# RFE_Cellularv2_1.net
KiCad netlist of a schematic drawn in Altium Designer
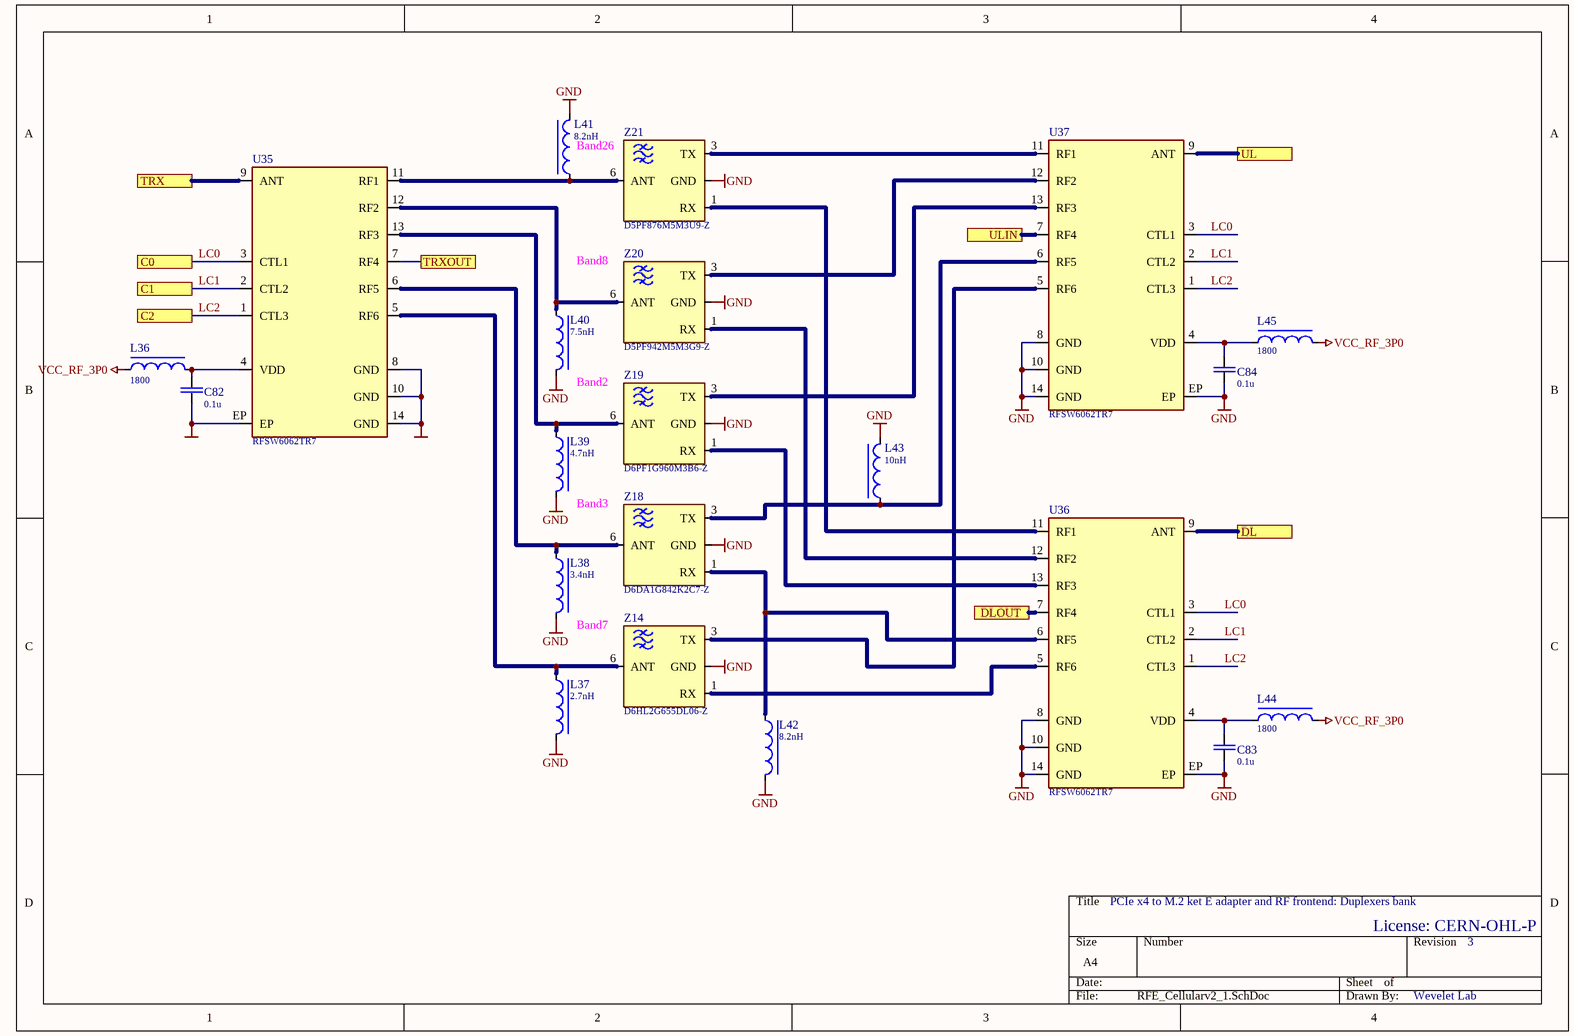
[diagram p0: RFE_Cellularv2_1.SchDoc]

(export (version "E")
  (design (tool "Eeschema 10.0.6"))
  (components
    (comp (ref "C82")
      (value "0.1u")
      (footprint "CAPC100X50X55L25N")
      (description "Capacitor, 0.1u, 25V, 10%, X7R, 0402")
      (fields
        (field (name "MANUFACTURER") "Murata Electronics")
        (field (name "Comment") "GRM155R71E104KE14D")
      )
      (libsource (lib "Capacitors") (part "GRM155R71E104KE14D"))
    )
    (comp (ref "C83")
      (value "0.1u")
      (footprint "CAPC100X50X55L25N")
      (description "Capacitor, 0.1u, 25V, 10%, X7R, 0402")
      (fields
        (field (name "MANUFACTURER") "Murata Electronics")
        (field (name "Comment") "GRM155R71E104KE14D")
      )
      (libsource (lib "Capacitors") (part "GRM155R71E104KE14D"))
    )
    (comp (ref "C84")
      (value "0.1u")
      (footprint "CAPC100X50X55L25N")
      (description "Capacitor, 0.1u, 25V, 10%, X7R, 0402")
      (fields
        (field (name "MANUFACTURER") "Murata Electronics")
        (field (name "Comment") "GRM155R71E104KE14D")
      )
      (libsource (lib "Capacitors") (part "GRM155R71E104KE14D"))
    )
    (comp (ref "L36")
      (value "1800")
      (footprint "INDC100X60X60L30N")
      (description "Ferrite bead, 1800Ohm@100MHz, 0,2A, 2.2Ohm, -55/+125, SMD0402")
      (fields (field (name "MANUFACTURER") "Murata Electronics") (field (name "Comment") "BLM15HD182SN1D"))
      (libsource (lib "") (part "BLM15HD182SN1D_1"))
    )
    (comp (ref "L37")
      (value "2.7nH")
      (footprint "INDC60X30X35L15N")
      (description "Inductor, 2.7n, 0.5A, 200mOhm, -55/+125, SMD0201")
      (fields (field (name "MANUFACTURER") "TDK") (field (name "Comment") "MLG0603P2N7CT000"))
      (libsource (lib "Inductor_Transformer") (part "MLG0603P2N7CT000"))
    )
    (comp (ref "L38")
      (value "3.4nH")
      (footprint "INDC60X30X35L15N")
      (description "Inductor, 3.4n, -55/+125, SMD0201")
      (fields (field (name "MANUFACTURER") "TDK") (field (name "Comment") "MLG0603P3N4BT000"))
      (libsource (lib "Inductor_Transformer") (part "MLG0603P3N4BT000"))
    )
    (comp (ref "L39")
      (value "4.7nH")
      (footprint "INDC60X30X35L15N")
      (description "Inductor, 4.7n, -55/+125, SMD0201")
      (fields (field (name "MANUFACTURER") "TDK") (field (name "Comment") "MLG0603P4N7HT000"))
      (libsource (lib "Inductor_Transformer") (part "MLG0603P4N7HT000"))
    )
    (comp (ref "L40")
      (value "7.5nH")
      (footprint "INDC60X30X35L15N")
      (description "Inductor, 7.5n, -55/+125, SMD0201")
      (fields (field (name "MANUFACTURER") "TDK") (field (name "Comment") "MLG0603P7N5HT000"))
      (libsource (lib "Inductor_Transformer") (part "MLG0603P7N5HT000"))
    )
    (comp (ref "L41")
      (value "8.2nH")
      (footprint "INDC60X30X35L15N")
      (description "Inductor, 8.2n, -55/+125, SMD0201")
      (fields (field (name "MANUFACTURER") "TDK") (field (name "Comment") "MLG0603P8N2HT000"))
      (libsource (lib "Inductor_Transformer") (part "MLG0603P8N2HT000"))
    )
    (comp (ref "L42")
      (value "8.2nH")
      (footprint "INDC60X30X35L15N")
      (description "Inductor, 8.2n, -55/+125, SMD0201")
      (fields (field (name "MANUFACTURER") "TDK") (field (name "Comment") "MLG0603P8N2HT000"))
      (libsource (lib "Inductor_Transformer") (part "MLG0603P8N2HT000"))
    )
    (comp (ref "L43")
      (value "10nH")
      (footprint "INDC60X30X35L15N")
      (description "Inductor, 10n, -55/+125, SMD0201")
      (fields (field (name "MANUFACTURER") "TDK") (field (name "Comment") "MLG0603P10NHT000"))
      (libsource (lib "Inductor_Transformer") (part "MLG0603P10NHT000"))
    )
    (comp (ref "L44")
      (value "1800")
      (footprint "INDC100X60X60L30N")
      (description "Ferrite bead, 1800Ohm@100MHz, 0,2A, 2.2Ohm, -55/+125, SMD0402")
      (fields (field (name "MANUFACTURER") "Murata Electronics") (field (name "Comment") "BLM15HD182SN1D"))
      (libsource (lib "Inductor_Transformer") (part "BLM15HD182SN1D"))
    )
    (comp (ref "L45")
      (value "1800")
      (footprint "INDC100X60X60L30N")
      (description "Ferrite bead, 1800Ohm@100MHz, 0,2A, 2.2Ohm, -55/+125, SMD0402")
      (fields (field (name "MANUFACTURER") "Murata Electronics") (field (name "Comment") "BLM15HD182SN1D"))
      (libsource (lib "Inductor_Transformer") (part "BLM15HD182SN1D"))
    )
    (comp (ref "U35")
      (value "RFSW6062TR7")
      (footprint "QFN15P40_200X200X60L21X18T100N")
      (description "IC, Switch, SP6T, 5-6000MHz, -40/+85,  \r\n14-QFN")
      (fields (field (name "MANUFACTURER") "Qorvo"))
      (libsource (lib "IC Digital") (part "RFSW6062"))
    )
    (comp (ref "U36")
      (value "RFSW6062TR7")
      (footprint "QFN15P40_200X200X60L21X18T100N")
      (description "IC, Switch, SP6T, 5-6000MHz, -40/+85,  \r\n14-QFN")
      (fields (field (name "MANUFACTURER") "Qorvo"))
      (libsource (lib "") (part "RFSW6062_1"))
    )
    (comp (ref "U37")
      (value "RFSW6062TR7")
      (footprint "QFN15P40_200X200X60L21X18T100N")
      (description "IC, Switch, SP6T, 5-6000MHz, -40/+85,  \r\n14-QFN")
      (fields (field (name "MANUFACTURER") "Qorvo"))
      (libsource (lib "") (part "RFSW6062_1"))
    )
    (comp (ref "Z14")
      (value "D6HL2G655DL06-Z")
      (footprint "TAIYO_YUDEN_SMD-9")
      (description "RF DUPLEXER, Band 7, -20/+85, SMD9")
      (fields (field (name "MANUFACTURER") "TAIYO YUDEN"))
      (libsource (lib "Inductor_Transformer") (part "D6HL2G655DL06"))
    )
    (comp (ref "Z18")
      (value "D6DA1G842K2C7-Z")
      (footprint "TAIYO_YUDEN_SMD-8")
      (description "RF DUPLEXER, Band 3, -20/+85, SMD8")
      (fields (field (name "MANUFACTURER") "TAIYO YUDEN"))
      (libsource (lib "Inductor_Transformer") (part "D6DA1G842K2C7"))
    )
    (comp (ref "Z19")
      (value "D6PF1G960M3B6-Z")
      (footprint "TAIYO_YUDEN_SMD-9")
      (description "RF DUPLEXER, Band 2, -20/+85, SMD9")
      (fields (field (name "MANUFACTURER") "TAIYO YUDEN"))
      (libsource (lib "Inductor_Transformer") (part "D6PF1G960M3B6"))
    )
    (comp (ref "Z20")
      (value "D5PF942M5M3G9-Z")
      (footprint "TAIYO_YUDEN_SMD-9")
      (description "RF DUPLEXER, Band 8, -20/+85, SMD9")
      (fields (field (name "MANUFACTURER") "TAIYO YUDEN"))
      (libsource (lib "Inductor_Transformer") (part "D5PF942M5M3G9"))
    )
    (comp (ref "Z21")
      (value "D5PF876M5M3U9-Z")
      (footprint "TAIYO_YUDEN_SMD-9")
      (description "RF DUPLEXER, Band 26, -20/+85, SMD9")
      (fields (field (name "MANUFACTURER") "TAIYO YUDEN"))
      (libsource (lib "Inductor_Transformer") (part "D5PF876M5M3U9"))
    )
  )
  (nets
    (net (code "1") (name "/DL") (class "Default")
      (node (ref "U36") (pin "9") (pinfunction "ANT_9") (pintype "passive"))
    )
    (net (code "2") (name "/DLOUT") (class "Default")
      (node (ref "U36") (pin "7") (pinfunction "RF4_7") (pintype "passive"))
    )
    (net (code "3") (name "/LC0") (class "Default")
      (node (ref "U35") (pin "3") (pinfunction "CTL1_3") (pintype "passive"))
      (node (ref "U36") (pin "3") (pinfunction "CTL1_3") (pintype "passive"))
      (node (ref "U37") (pin "3") (pinfunction "CTL1_3") (pintype "passive"))
    )
    (net (code "4") (name "/LC1") (class "Default")
      (node (ref "U35") (pin "2") (pinfunction "CTL2_2") (pintype "passive"))
      (node (ref "U36") (pin "2") (pinfunction "CTL2_2") (pintype "passive"))
      (node (ref "U37") (pin "2") (pinfunction "CTL2_2") (pintype "passive"))
    )
    (net (code "5") (name "/LC2") (class "Default")
      (node (ref "U35") (pin "1") (pinfunction "CTL3_1") (pintype "passive"))
      (node (ref "U36") (pin "1") (pinfunction "CTL3_1") (pintype "passive"))
      (node (ref "U37") (pin "1") (pinfunction "CTL3_1") (pintype "passive"))
    )
    (net (code "6") (name "/TRX") (class "Default")
      (node (ref "U35") (pin "9") (pinfunction "ANT_9") (pintype "passive"))
    )
    (net (code "7") (name "/TRXOUT") (class "Default")
      (node (ref "U35") (pin "7") (pinfunction "RF4_7") (pintype "passive"))
    )
    (net (code "8") (name "/UL") (class "Default")
      (node (ref "U37") (pin "9") (pinfunction "ANT_9") (pintype "passive"))
    )
    (net (code "9") (name "/ULIN") (class "Default")
      (node (ref "U37") (pin "7") (pinfunction "RF4_7") (pintype "passive"))
    )
    (net (code "10") (name "GND") (class "Default")
      (node (ref "C82") (pin "2") (pinfunction "2_2") (pintype "passive"))
      (node (ref "C83") (pin "2") (pinfunction "2_2") (pintype "passive"))
      (node (ref "C84") (pin "2") (pinfunction "2_2") (pintype "passive"))
      (node (ref "L37") (pin "2") (pinfunction "2_2") (pintype "passive"))
      (node (ref "L38") (pin "2") (pinfunction "2_2") (pintype "passive"))
      (node (ref "L39") (pin "2") (pinfunction "2_2") (pintype "passive"))
      (node (ref "L40") (pin "2") (pinfunction "2_2") (pintype "passive"))
      (node (ref "L41") (pin "2") (pinfunction "2_2") (pintype "passive"))
      (node (ref "L42") (pin "2") (pinfunction "2_2") (pintype "passive"))
      (node (ref "L43") (pin "2") (pinfunction "2_2") (pintype "passive"))
      (node (ref "U35") (pin "10") (pinfunction "GND_10") (pintype "passive"))
      (node (ref "U35") (pin "14") (pinfunction "GND_14") (pintype "passive"))
      (node (ref "U35") (pin "8") (pinfunction "GND_8") (pintype "passive"))
      (node (ref "U35") (pin "EP") (pinfunction "EP_EP") (pintype "passive"))
      (node (ref "U36") (pin "10") (pinfunction "GND_10") (pintype "passive"))
      (node (ref "U36") (pin "14") (pinfunction "GND_14") (pintype "passive"))
      (node (ref "U36") (pin "8") (pinfunction "GND_8") (pintype "passive"))
      (node (ref "U36") (pin "EP") (pinfunction "EP_EP") (pintype "passive"))
      (node (ref "U37") (pin "10") (pinfunction "GND_10") (pintype "passive"))
      (node (ref "U37") (pin "14") (pinfunction "GND_14") (pintype "passive"))
      (node (ref "U37") (pin "8") (pinfunction "GND_8") (pintype "passive"))
      (node (ref "U37") (pin "EP") (pinfunction "EP_EP") (pintype "passive"))
      (node (ref "Z14") (pin "GND") (pinfunction "GND_GND") (pintype "passive"))
      (node (ref "Z18") (pin "GND") (pinfunction "GND_GND") (pintype "passive"))
      (node (ref "Z19") (pin "GND") (pinfunction "GND_GND") (pintype "passive"))
      (node (ref "Z20") (pin "GND") (pinfunction "GND_GND") (pintype "passive"))
      (node (ref "Z21") (pin "GND") (pinfunction "GND_GND") (pintype "passive"))
    )
    (net (code "11") (name "Net-(U35-RF1)") (class "Default")
      (node (ref "L41") (pin "1") (pinfunction "1_1") (pintype "passive"))
      (node (ref "U35") (pin "11") (pinfunction "RF1_11") (pintype "passive"))
      (node (ref "Z21") (pin "6") (pinfunction "ANT_6") (pintype "passive"))
    )
    (net (code "12") (name "Net-(U35-RF2)") (class "Default")
      (node (ref "L40") (pin "1") (pinfunction "1_1") (pintype "passive"))
      (node (ref "U35") (pin "12") (pinfunction "RF2_12") (pintype "passive"))
      (node (ref "Z20") (pin "6") (pinfunction "ANT_6") (pintype "passive"))
    )
    (net (code "13") (name "Net-(U35-RF3)") (class "Default")
      (node (ref "L39") (pin "1") (pinfunction "1_1") (pintype "passive"))
      (node (ref "U35") (pin "13") (pinfunction "RF3_13") (pintype "passive"))
      (node (ref "Z19") (pin "6") (pinfunction "ANT_6") (pintype "passive"))
    )
    (net (code "14") (name "Net-(U35-RF5)") (class "Default")
      (node (ref "L38") (pin "1") (pinfunction "1_1") (pintype "passive"))
      (node (ref "U35") (pin "6") (pinfunction "RF5_6") (pintype "passive"))
      (node (ref "Z18") (pin "6") (pinfunction "ANT_6") (pintype "passive"))
    )
    (net (code "15") (name "Net-(U35-RF6)") (class "Default")
      (node (ref "L37") (pin "1") (pinfunction "1_1") (pintype "passive"))
      (node (ref "U35") (pin "5") (pinfunction "RF6_5") (pintype "passive"))
      (node (ref "Z14") (pin "6") (pinfunction "ANT_6") (pintype "passive"))
    )
    (net (code "16") (name "Net-(U35-VDD)") (class "Default")
      (node (ref "C82") (pin "1") (pinfunction "1_1") (pintype "passive"))
      (node (ref "L36") (pin "1") (pinfunction "1_1") (pintype "passive"))
      (node (ref "U35") (pin "4") (pinfunction "VDD_4") (pintype "passive"))
    )
    (net (code "17") (name "Net-(U36-RF1)") (class "Default")
      (node (ref "U36") (pin "11") (pinfunction "RF1_11") (pintype "passive"))
      (node (ref "Z21") (pin "1") (pinfunction "RX_1") (pintype "passive"))
    )
    (net (code "18") (name "Net-(U36-RF2)") (class "Default")
      (node (ref "U36") (pin "12") (pinfunction "RF2_12") (pintype "passive"))
      (node (ref "Z20") (pin "1") (pinfunction "RX_1") (pintype "passive"))
    )
    (net (code "19") (name "Net-(U36-RF3)") (class "Default")
      (node (ref "U36") (pin "13") (pinfunction "RF3_13") (pintype "passive"))
      (node (ref "Z19") (pin "1") (pinfunction "RX_1") (pintype "passive"))
    )
    (net (code "20") (name "Net-(U36-RF5)") (class "Default")
      (node (ref "L42") (pin "1") (pinfunction "1_1") (pintype "passive"))
      (node (ref "U36") (pin "6") (pinfunction "RF5_6") (pintype "passive"))
      (node (ref "Z18") (pin "1") (pinfunction "RX_1") (pintype "passive"))
    )
    (net (code "21") (name "Net-(U36-RF6)") (class "Default")
      (node (ref "U36") (pin "5") (pinfunction "RF6_5") (pintype "passive"))
      (node (ref "Z14") (pin "1") (pinfunction "RX_1") (pintype "passive"))
    )
    (net (code "22") (name "Net-(U36-VDD)") (class "Default")
      (node (ref "C83") (pin "1") (pinfunction "1_1") (pintype "passive"))
      (node (ref "L44") (pin "1") (pinfunction "1_1") (pintype "passive"))
      (node (ref "U36") (pin "4") (pinfunction "VDD_4") (pintype "passive"))
    )
    (net (code "23") (name "Net-(U37-RF1)") (class "Default")
      (node (ref "U37") (pin "11") (pinfunction "RF1_11") (pintype "passive"))
      (node (ref "Z21") (pin "3") (pinfunction "TX_3") (pintype "passive"))
    )
    (net (code "24") (name "Net-(U37-RF2)") (class "Default")
      (node (ref "U37") (pin "12") (pinfunction "RF2_12") (pintype "passive"))
      (node (ref "Z20") (pin "3") (pinfunction "TX_3") (pintype "passive"))
    )
    (net (code "25") (name "Net-(U37-RF3)") (class "Default")
      (node (ref "U37") (pin "13") (pinfunction "RF3_13") (pintype "passive"))
      (node (ref "Z19") (pin "3") (pinfunction "TX_3") (pintype "passive"))
    )
    (net (code "26") (name "Net-(U37-RF5)") (class "Default")
      (node (ref "L43") (pin "1") (pinfunction "1_1") (pintype "passive"))
      (node (ref "U37") (pin "6") (pinfunction "RF5_6") (pintype "passive"))
      (node (ref "Z18") (pin "3") (pinfunction "TX_3") (pintype "passive"))
    )
    (net (code "27") (name "Net-(U37-RF6)") (class "Default")
      (node (ref "U37") (pin "5") (pinfunction "RF6_5") (pintype "passive"))
      (node (ref "Z14") (pin "3") (pinfunction "TX_3") (pintype "passive"))
    )
    (net (code "28") (name "Net-(U37-VDD)") (class "Default")
      (node (ref "C84") (pin "1") (pinfunction "1_1") (pintype "passive"))
      (node (ref "L45") (pin "1") (pinfunction "1_1") (pintype "passive"))
      (node (ref "U37") (pin "4") (pinfunction "VDD_4") (pintype "passive"))
    )
    (net (code "29") (name "VCC_RF_3P0") (class "Default")
      (node (ref "L36") (pin "2") (pinfunction "2_2") (pintype "passive"))
      (node (ref "L44") (pin "2") (pinfunction "2_2") (pintype "passive"))
      (node (ref "L45") (pin "2") (pinfunction "2_2") (pintype "passive"))
    )
  )
)
